# scenes_bus.net
KiCad netlist of a schematic drawn in EAGLE
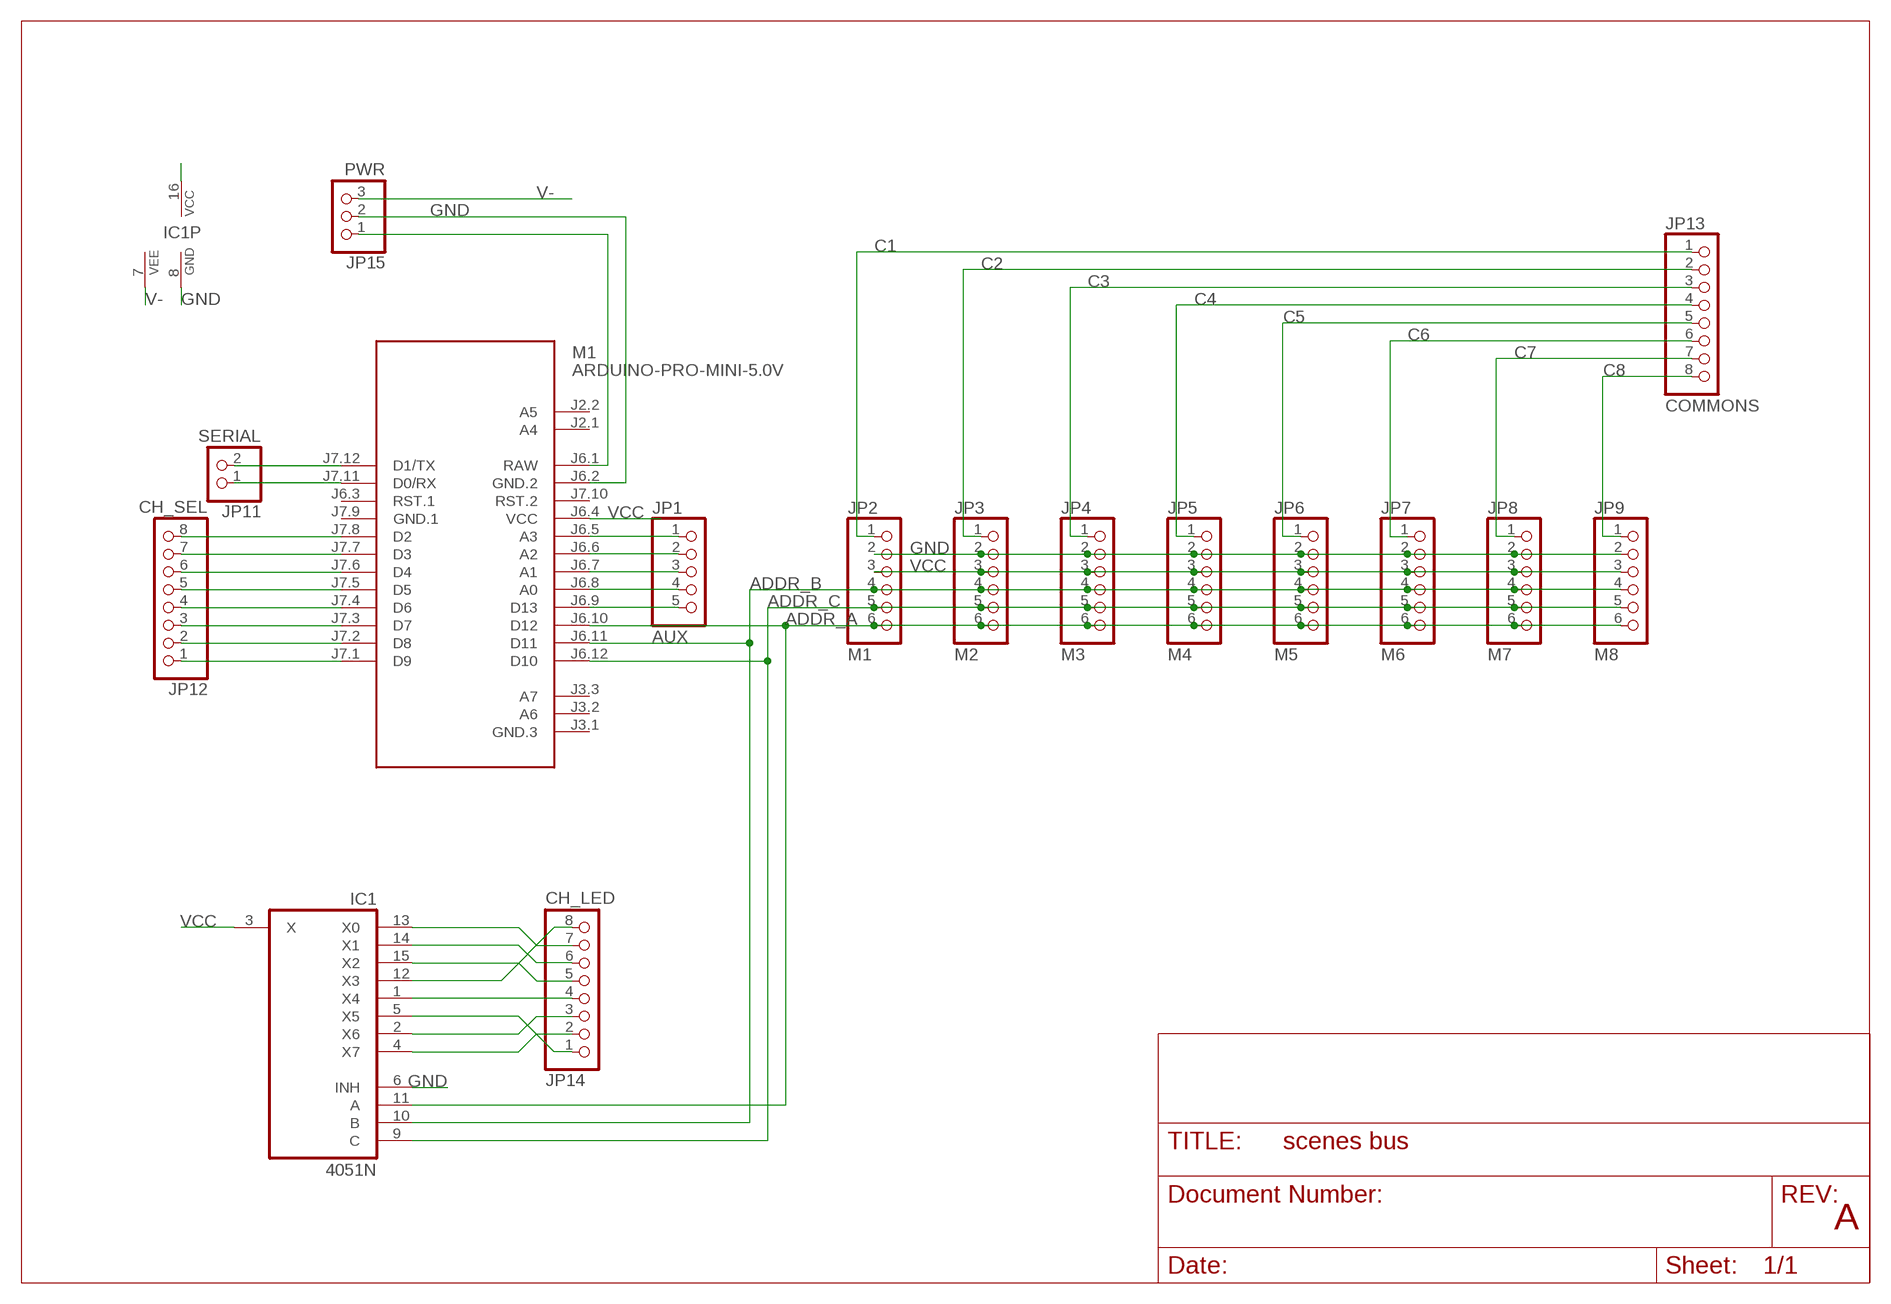
[diagram p0: schematic, sheet 1]

(export (version "E")
  (design (tool "Eeschema 10.0.6"))
  (components
    (comp (ref "IC1")
      (value "4051N")
      (footprint "eagle-import:DIL16")
      (libsource (lib "eagle-import") (part "4051N"))
    )
    (comp (ref "JP1")
      (value "AUX")
      (footprint "eagle-import:1X05")
      (libsource (lib "eagle-import") (part "PINHD-1X5"))
    )
    (comp (ref "JP2")
      (value "M1")
      (footprint "eagle-import:1X06")
      (libsource (lib "eagle-import") (part "PINHD-1X6"))
    )
    (comp (ref "JP3")
      (value "M2")
      (footprint "eagle-import:1X06")
      (libsource (lib "eagle-import") (part "PINHD-1X6"))
    )
    (comp (ref "JP4")
      (value "M3")
      (footprint "eagle-import:1X06")
      (libsource (lib "eagle-import") (part "PINHD-1X6"))
    )
    (comp (ref "JP5")
      (value "M4")
      (footprint "eagle-import:1X06")
      (libsource (lib "eagle-import") (part "PINHD-1X6"))
    )
    (comp (ref "JP6")
      (value "M5")
      (footprint "eagle-import:1X06")
      (libsource (lib "eagle-import") (part "PINHD-1X6"))
    )
    (comp (ref "JP7")
      (value "M6")
      (footprint "eagle-import:1X06")
      (libsource (lib "eagle-import") (part "PINHD-1X6"))
    )
    (comp (ref "JP8")
      (value "M7")
      (footprint "eagle-import:1X06")
      (libsource (lib "eagle-import") (part "PINHD-1X6"))
    )
    (comp (ref "JP9")
      (value "M8")
      (footprint "eagle-import:1X06")
      (libsource (lib "eagle-import") (part "PINHD-1X6"))
    )
    (comp (ref "JP11")
      (value "SERIAL")
      (footprint "eagle-import:1X02")
      (libsource (lib "eagle-import") (part "PINHD-1X2"))
    )
    (comp (ref "JP12")
      (value "CH_SEL")
      (footprint "eagle-import:1X08")
      (libsource (lib "eagle-import") (part "PINHD-1X8"))
    )
    (comp (ref "JP13")
      (value "COMMONS")
      (footprint "eagle-import:1X08")
      (libsource (lib "eagle-import") (part "PINHD-1X8"))
    )
    (comp (ref "JP14")
      (value "CH_LED")
      (footprint "eagle-import:1X08")
      (libsource (lib "eagle-import") (part "PINHD-1X8"))
    )
    (comp (ref "JP15")
      (value "PWR")
      (footprint "eagle-import:1X03")
      (libsource (lib "eagle-import") (part "PINHD-1X3"))
    )
    (comp (ref "M1")
      (value "ARDUINO-PRO-MINI-5.0V")
      (footprint "eagle-import:ARDUINO-PRO-MINI#NP")
      (libsource (lib "eagle-import") (part "ARDUINO-PRO-MINI-#NP5.0V"))
    )
  )
  (nets
    (net (code "1") (name "/ADDR_A") (class "Default")
      (node (ref "IC1") (pin "11") (pinfunction "A_11") (pintype "input"))
      (node (ref "JP2") (pin "6") (pinfunction "6_6") (pintype "passive"))
      (node (ref "JP3") (pin "6") (pinfunction "6_6") (pintype "passive"))
      (node (ref "JP4") (pin "6") (pinfunction "6_6") (pintype "passive"))
      (node (ref "JP5") (pin "6") (pinfunction "6_6") (pintype "passive"))
      (node (ref "JP6") (pin "6") (pinfunction "6_6") (pintype "passive"))
      (node (ref "JP7") (pin "6") (pinfunction "6_6") (pintype "passive"))
      (node (ref "JP8") (pin "6") (pinfunction "6_6") (pintype "passive"))
      (node (ref "JP9") (pin "6") (pinfunction "6_6") (pintype "passive"))
      (node (ref "M1") (pin "J6.10") (pinfunction "D12_J6.10") (pintype "bidirectional"))
    )
    (net (code "2") (name "/ADDR_B") (class "Default")
      (node (ref "IC1") (pin "10") (pinfunction "B_10") (pintype "input"))
      (node (ref "JP2") (pin "4") (pinfunction "4_4") (pintype "passive"))
      (node (ref "JP3") (pin "4") (pinfunction "4_4") (pintype "passive"))
      (node (ref "JP4") (pin "4") (pinfunction "4_4") (pintype "passive"))
      (node (ref "JP5") (pin "4") (pinfunction "4_4") (pintype "passive"))
      (node (ref "JP6") (pin "4") (pinfunction "4_4") (pintype "passive"))
      (node (ref "JP7") (pin "4") (pinfunction "4_4") (pintype "passive"))
      (node (ref "JP8") (pin "4") (pinfunction "4_4") (pintype "passive"))
      (node (ref "JP9") (pin "4") (pinfunction "4_4") (pintype "passive"))
      (node (ref "M1") (pin "J6.11") (pinfunction "D11_J6.11") (pintype "bidirectional"))
    )
    (net (code "3") (name "/ADDR_C") (class "Default")
      (node (ref "IC1") (pin "9") (pinfunction "C_9") (pintype "input"))
      (node (ref "JP2") (pin "5") (pinfunction "5_5") (pintype "passive"))
      (node (ref "JP3") (pin "5") (pinfunction "5_5") (pintype "passive"))
      (node (ref "JP4") (pin "5") (pinfunction "5_5") (pintype "passive"))
      (node (ref "JP5") (pin "5") (pinfunction "5_5") (pintype "passive"))
      (node (ref "JP6") (pin "5") (pinfunction "5_5") (pintype "passive"))
      (node (ref "JP7") (pin "5") (pinfunction "5_5") (pintype "passive"))
      (node (ref "JP8") (pin "5") (pinfunction "5_5") (pintype "passive"))
      (node (ref "JP9") (pin "5") (pinfunction "5_5") (pintype "passive"))
      (node (ref "M1") (pin "J6.12") (pinfunction "D10_J6.12") (pintype "bidirectional"))
    )
    (net (code "4") (name "/C1") (class "Default")
      (node (ref "JP13") (pin "1") (pinfunction "1_1") (pintype "passive"))
      (node (ref "JP2") (pin "1") (pinfunction "1_1") (pintype "passive"))
    )
    (net (code "5") (name "/C2") (class "Default")
      (node (ref "JP13") (pin "2") (pinfunction "2_2") (pintype "passive"))
      (node (ref "JP3") (pin "1") (pinfunction "1_1") (pintype "passive"))
    )
    (net (code "6") (name "/C3") (class "Default")
      (node (ref "JP13") (pin "3") (pinfunction "3_3") (pintype "passive"))
      (node (ref "JP4") (pin "1") (pinfunction "1_1") (pintype "passive"))
    )
    (net (code "7") (name "/C4") (class "Default")
      (node (ref "JP13") (pin "4") (pinfunction "4_4") (pintype "passive"))
      (node (ref "JP5") (pin "1") (pinfunction "1_1") (pintype "passive"))
    )
    (net (code "8") (name "/C5") (class "Default")
      (node (ref "JP13") (pin "5") (pinfunction "5_5") (pintype "passive"))
      (node (ref "JP6") (pin "1") (pinfunction "1_1") (pintype "passive"))
    )
    (net (code "9") (name "/C6") (class "Default")
      (node (ref "JP13") (pin "6") (pinfunction "6_6") (pintype "passive"))
      (node (ref "JP7") (pin "1") (pinfunction "1_1") (pintype "passive"))
    )
    (net (code "10") (name "/C7") (class "Default")
      (node (ref "JP13") (pin "7") (pinfunction "7_7") (pintype "passive"))
      (node (ref "JP8") (pin "1") (pinfunction "1_1") (pintype "passive"))
    )
    (net (code "11") (name "/C8") (class "Default")
      (node (ref "JP13") (pin "8") (pinfunction "8_8") (pintype "passive"))
      (node (ref "JP9") (pin "1") (pinfunction "1_1") (pintype "passive"))
    )
    (net (code "12") (name "/GND") (class "Default")
      (node (ref "IC1") (pin "6") (pinfunction "INH_6") (pintype "input"))
      (node (ref "IC1") (pin "8") (pinfunction "GND_8") (pintype "power_in"))
      (node (ref "JP15") (pin "2") (pinfunction "2_2") (pintype "passive"))
      (node (ref "JP2") (pin "2") (pinfunction "2_2") (pintype "passive"))
      (node (ref "JP3") (pin "2") (pinfunction "2_2") (pintype "passive"))
      (node (ref "JP4") (pin "2") (pinfunction "2_2") (pintype "passive"))
      (node (ref "JP5") (pin "2") (pinfunction "2_2") (pintype "passive"))
      (node (ref "JP6") (pin "2") (pinfunction "2_2") (pintype "passive"))
      (node (ref "JP7") (pin "2") (pinfunction "2_2") (pintype "passive"))
      (node (ref "JP8") (pin "2") (pinfunction "2_2") (pintype "passive"))
      (node (ref "JP9") (pin "2") (pinfunction "2_2") (pintype "passive"))
      (node (ref "M1") (pin "J6.2") (pinfunction "GND.2_J6.2") (pintype "power_in"))
    )
    (net (code "13") (name "/GND.1") (class "Default")
      (node (ref "M1") (pin "J7.9") (pinfunction "GND.1_J7.9") (pintype "power_in"))
    )
    (net (code "14") (name "/V-") (class "Default")
      (node (ref "IC1") (pin "7") (pinfunction "VEE_7") (pintype "power_in"))
      (node (ref "JP15") (pin "3") (pinfunction "3_3") (pintype "passive"))
    )
    (net (code "15") (name "/VCC") (class "Default")
      (node (ref "IC1") (pin "16") (pinfunction "VCC_16") (pintype "power_in"))
      (node (ref "IC1") (pin "3") (pinfunction "X_3") (pintype "bidirectional"))
      (node (ref "JP2") (pin "3") (pinfunction "3_3") (pintype "passive"))
      (node (ref "JP3") (pin "3") (pinfunction "3_3") (pintype "passive"))
      (node (ref "JP4") (pin "3") (pinfunction "3_3") (pintype "passive"))
      (node (ref "JP5") (pin "3") (pinfunction "3_3") (pintype "passive"))
      (node (ref "JP6") (pin "3") (pinfunction "3_3") (pintype "passive"))
      (node (ref "JP7") (pin "3") (pinfunction "3_3") (pintype "passive"))
      (node (ref "JP8") (pin "3") (pinfunction "3_3") (pintype "passive"))
      (node (ref "JP9") (pin "3") (pinfunction "3_3") (pintype "passive"))
      (node (ref "M1") (pin "J6.4") (pinfunction "VCC_J6.4") (pintype "power_in"))
    )
    (net (code "16") (name "Net-(IC1A-X0)") (class "Default")
      (node (ref "IC1") (pin "13") (pinfunction "X0_13") (pintype "bidirectional"))
      (node (ref "JP14") (pin "7") (pinfunction "7_7") (pintype "passive"))
    )
    (net (code "17") (name "Net-(IC1A-X1)") (class "Default")
      (node (ref "IC1") (pin "14") (pinfunction "X1_14") (pintype "bidirectional"))
      (node (ref "JP14") (pin "6") (pinfunction "6_6") (pintype "passive"))
    )
    (net (code "18") (name "Net-(IC1A-X2)") (class "Default")
      (node (ref "IC1") (pin "15") (pinfunction "X2_15") (pintype "bidirectional"))
      (node (ref "JP14") (pin "5") (pinfunction "5_5") (pintype "passive"))
    )
    (net (code "19") (name "Net-(IC1A-X3)") (class "Default")
      (node (ref "IC1") (pin "12") (pinfunction "X3_12") (pintype "bidirectional"))
      (node (ref "JP14") (pin "8") (pinfunction "8_8") (pintype "passive"))
    )
    (net (code "20") (name "Net-(IC1A-X4)") (class "Default")
      (node (ref "IC1") (pin "1") (pinfunction "X4_1") (pintype "bidirectional"))
      (node (ref "JP14") (pin "4") (pinfunction "4_4") (pintype "passive"))
    )
    (net (code "21") (name "Net-(IC1A-X5)") (class "Default")
      (node (ref "IC1") (pin "5") (pinfunction "X5_5") (pintype "bidirectional"))
      (node (ref "JP14") (pin "1") (pinfunction "1_1") (pintype "passive"))
    )
    (net (code "22") (name "Net-(IC1A-X6)") (class "Default")
      (node (ref "IC1") (pin "2") (pinfunction "X6_2") (pintype "bidirectional"))
      (node (ref "JP14") (pin "3") (pinfunction "3_3") (pintype "passive"))
    )
    (net (code "23") (name "Net-(IC1A-X7)") (class "Default")
      (node (ref "IC1") (pin "4") (pinfunction "X7_4") (pintype "bidirectional"))
      (node (ref "JP14") (pin "2") (pinfunction "2_2") (pintype "passive"))
    )
    (net (code "24") (name "Net-(M1-A0)") (class "Default")
      (node (ref "JP1") (pin "4") (pinfunction "4_4") (pintype "passive"))
      (node (ref "M1") (pin "J6.8") (pinfunction "A0_J6.8") (pintype "bidirectional"))
    )
    (net (code "25") (name "Net-(M1-A1)") (class "Default")
      (node (ref "JP1") (pin "3") (pinfunction "3_3") (pintype "passive"))
      (node (ref "M1") (pin "J6.7") (pinfunction "A1_J6.7") (pintype "bidirectional"))
    )
    (net (code "26") (name "Net-(M1-A2)") (class "Default")
      (node (ref "JP1") (pin "2") (pinfunction "2_2") (pintype "passive"))
      (node (ref "M1") (pin "J6.6") (pinfunction "A2_J6.6") (pintype "bidirectional"))
    )
    (net (code "27") (name "Net-(M1-A3)") (class "Default")
      (node (ref "JP1") (pin "1") (pinfunction "1_1") (pintype "passive"))
      (node (ref "M1") (pin "J6.5") (pinfunction "A3_J6.5") (pintype "bidirectional"))
    )
    (net (code "28") (name "Net-(M1-D0{slash}RX)") (class "Default")
      (node (ref "JP11") (pin "1") (pinfunction "1_1") (pintype "passive"))
      (node (ref "M1") (pin "J7.11") (pinfunction "D0/RX_J7.11") (pintype "bidirectional"))
    )
    (net (code "29") (name "Net-(M1-D1{slash}TX)") (class "Default")
      (node (ref "JP11") (pin "2") (pinfunction "2_2") (pintype "passive"))
      (node (ref "M1") (pin "J7.12") (pinfunction "D1/TX_J7.12") (pintype "bidirectional"))
    )
    (net (code "30") (name "Net-(M1-D2)") (class "Default")
      (node (ref "JP12") (pin "8") (pinfunction "8_8") (pintype "passive"))
      (node (ref "M1") (pin "J7.8") (pinfunction "D2_J7.8") (pintype "bidirectional"))
    )
    (net (code "31") (name "Net-(M1-D3)") (class "Default")
      (node (ref "JP12") (pin "7") (pinfunction "7_7") (pintype "passive"))
      (node (ref "M1") (pin "J7.7") (pinfunction "D3_J7.7") (pintype "bidirectional"))
    )
    (net (code "32") (name "Net-(M1-D4)") (class "Default")
      (node (ref "JP12") (pin "6") (pinfunction "6_6") (pintype "passive"))
      (node (ref "M1") (pin "J7.6") (pinfunction "D4_J7.6") (pintype "bidirectional"))
    )
    (net (code "33") (name "Net-(M1-D5)") (class "Default")
      (node (ref "JP12") (pin "5") (pinfunction "5_5") (pintype "passive"))
      (node (ref "M1") (pin "J7.5") (pinfunction "D5_J7.5") (pintype "bidirectional"))
    )
    (net (code "34") (name "Net-(M1-D6)") (class "Default")
      (node (ref "JP12") (pin "4") (pinfunction "4_4") (pintype "passive"))
      (node (ref "M1") (pin "J7.4") (pinfunction "D6_J7.4") (pintype "bidirectional"))
    )
    (net (code "35") (name "Net-(M1-D7)") (class "Default")
      (node (ref "JP12") (pin "3") (pinfunction "3_3") (pintype "passive"))
      (node (ref "M1") (pin "J7.3") (pinfunction "D7_J7.3") (pintype "bidirectional"))
    )
    (net (code "36") (name "Net-(M1-D8)") (class "Default")
      (node (ref "JP12") (pin "2") (pinfunction "2_2") (pintype "passive"))
      (node (ref "M1") (pin "J7.2") (pinfunction "D8_J7.2") (pintype "bidirectional"))
    )
    (net (code "37") (name "Net-(M1-D9)") (class "Default")
      (node (ref "JP12") (pin "1") (pinfunction "1_1") (pintype "passive"))
      (node (ref "M1") (pin "J7.1") (pinfunction "D9_J7.1") (pintype "bidirectional"))
    )
    (net (code "38") (name "Net-(M1-D13)") (class "Default")
      (node (ref "JP1") (pin "5") (pinfunction "5_5") (pintype "passive"))
      (node (ref "M1") (pin "J6.9") (pinfunction "D13_J6.9") (pintype "bidirectional"))
    )
    (net (code "39") (name "Net-(M1-RAW)") (class "Default")
      (node (ref "JP15") (pin "1") (pinfunction "1_1") (pintype "passive"))
      (node (ref "M1") (pin "J6.1") (pinfunction "RAW_J6.1") (pintype "power_in"))
    )
    (net (code "40") (name "unconnected-(M1-A4-PadJ2.1)") (class "Default")
      (node (ref "M1") (pin "J2.1") (pinfunction "A4_J2.1") (pintype "bidirectional"))
    )
    (net (code "41") (name "unconnected-(M1-A5-PadJ2.2)") (class "Default")
      (node (ref "M1") (pin "J2.2") (pinfunction "A5_J2.2") (pintype "bidirectional"))
    )
    (net (code "42") (name "unconnected-(M1-A6-PadJ3.2)") (class "Default")
      (node (ref "M1") (pin "J3.2") (pinfunction "A6_J3.2") (pintype "bidirectional"))
    )
    (net (code "43") (name "unconnected-(M1-A7-PadJ3.3)") (class "Default")
      (node (ref "M1") (pin "J3.3") (pinfunction "A7_J3.3") (pintype "bidirectional"))
    )
    (net (code "44") (name "unconnected-(M1-GND.3-PadJ3.1)") (class "Default")
      (node (ref "M1") (pin "J3.1") (pinfunction "GND.3_J3.1") (pintype "bidirectional"))
    )
    (net (code "45") (name "unconnected-(M1-RST.1-PadJ6.3)") (class "Default")
      (node (ref "M1") (pin "J6.3") (pinfunction "RST.1_J6.3") (pintype "bidirectional"))
    )
    (net (code "46") (name "unconnected-(M1-RST.2-PadJ7.10)") (class "Default")
      (node (ref "M1") (pin "J7.10") (pinfunction "RST.2_J7.10") (pintype "bidirectional"))
    )
  )
)
